# ADC_1CH.net
KiCad netlist of a schematic drawn in Altium Designer
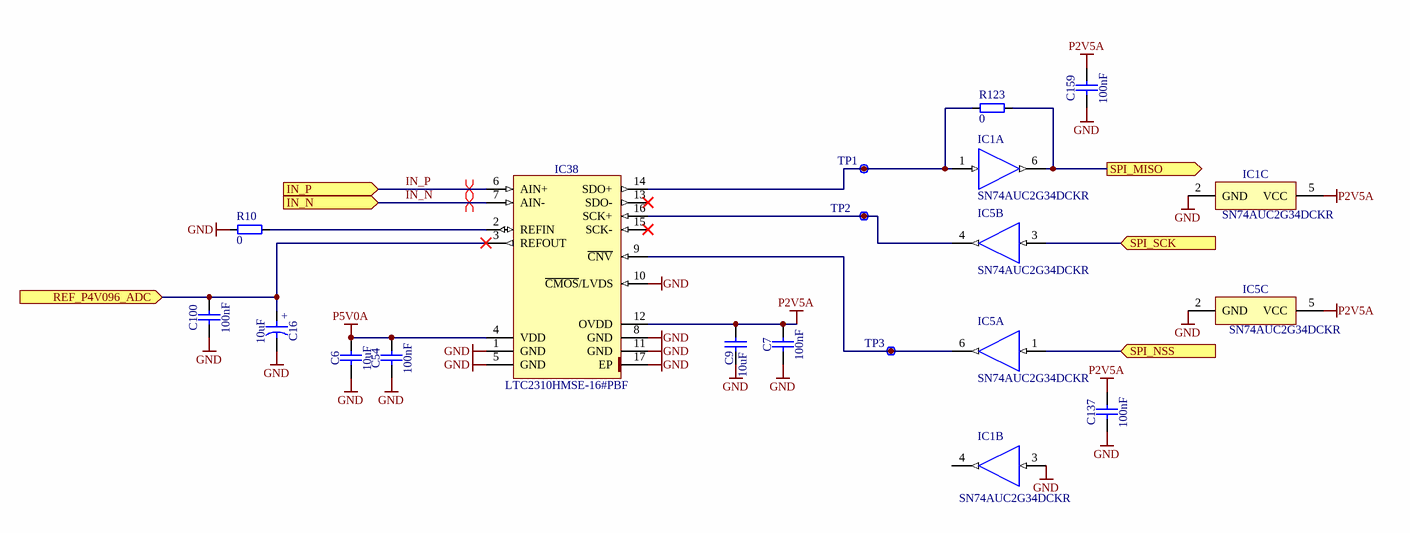
[diagram p0: ADC_1CH.SchDoc]

(export (version "E")
  (design (tool "Eeschema 10.0.6"))
  (components
    (comp (ref "C6")
      (value "10uF")
      (footprint "CAPC2012X95N")
      (description "Non-polarised capacitor")
      (fields
        (field (name "PART NUMBER") "CC0805_10UF_25V_10%_X5R")
        (field (name "VOLTAGE") "25V")
        (field (name "AUTHOR") "CERN DEM JLC")
      )
      (libsource (lib "Capacitors") (part "Capacitor - non polarized"))
    )
    (comp (ref "C7")
      (value "100nF")
      (footprint "CAPC1005X55N")
      (description "Non-polarised capacitor")
      (fields
        (field (name "PART NUMBER") "CC0402_100NF_16V_10%_X7R")
        (field (name "VOLTAGE") "16V")
        (field (name "AUTHOR") "CERN DEM JLC")
      )
      (libsource (lib "Capacitors") (part "Capacitor - non polarized"))
    )
    (comp (ref "C9")
      (value "10uF")
      (footprint "CAPC2012X95N")
      (description "Non-polarised capacitor")
      (fields
        (field (name "PART NUMBER") "CC0805_10UF_25V_10%_X5R")
        (field (name "VOLTAGE") "25V")
        (field (name "AUTHOR") "CERN DEM JLC")
      )
      (libsource (lib "Capacitors") (part "Capacitor - non polarized"))
    )
    (comp (ref "C16")
      (value "10uF")
      (footprint "CAPMP3216X180N")
      (description "Polarised capacitor")
      (fields
        (field (name "PART NUMBER") "CTE3216-18_10UF_16V_20%_AVX_TCJ")
        (field (name "VOLTAGE") "16V")
        (field (name "AUTHOR") "CERN DEM JLC")
      )
      (libsource (lib "Capacitors") (part "Capacitor - polarized"))
    )
    (comp (ref "C54")
      (value "100nF")
      (footprint "CAPC1005X55N")
      (description "Non-polarised capacitor")
      (fields
        (field (name "PART NUMBER") "CC0402_100NF_16V_10%_X7R")
        (field (name "VOLTAGE") "16V")
        (field (name "AUTHOR") "CERN DEM JLC")
      )
      (libsource (lib "Capacitors") (part "Capacitor - non polarized"))
    )
    (comp (ref "C100")
      (value "100nF")
      (footprint "CAPC1005X55N")
      (description "Non-polarised capacitor")
      (fields
        (field (name "PART NUMBER") "CC0402_100NF_16V_10%_X7R")
        (field (name "VOLTAGE") "16V")
        (field (name "AUTHOR") "CERN DEM JLC")
      )
      (libsource (lib "Capacitors") (part "Capacitor - non polarized"))
    )
    (comp (ref "C137")
      (value "100nF")
      (footprint "CAPC1005X55N")
      (description "Non-polarised capacitor")
      (fields
        (field (name "PART NUMBER") "CC0402_100NF_16V_10%_X7R")
        (field (name "VOLTAGE") "16V")
        (field (name "AUTHOR") "CERN DEM JLC")
      )
      (libsource (lib "Capacitors") (part "Capacitor - non polarized"))
    )
    (comp (ref "C159")
      (value "100nF")
      (footprint "CAPC1005X55N")
      (description "Non-polarised capacitor")
      (fields
        (field (name "PART NUMBER") "CC0402_100NF_16V_10%_X7R")
        (field (name "VOLTAGE") "16V")
        (field (name "AUTHOR") "CERN DEM JLC")
      )
      (libsource (lib "Capacitors") (part "Capacitor - non polarized"))
    )
    (comp (ref "IC1")
      (value "SN74AUC2G34DCKR")
      (footprint "DCK0006A_M")
      (description "Dual Buffer Gate, DCK0006A, LARGE T&R")
      (fields (field (name "PART NUMBER") "SN74AUC2G34"))
      (libsource (lib "") (part "TI-SN74XXX2GXXX-6_A_1"))
    )
    (comp (ref "IC5")
      (value "SN74AUC2G34DCKR")
      (footprint "DCK0006A_M")
      (description "Dual Buffer Gate, DCK0006A, LARGE T&R")
      (fields (field (name "PART NUMBER") "SN74AUC2G34"))
      (libsource (lib "Altium Content Vault") (part "TI-SN74XXX2GXXX-6_A"))
    )
    (comp (ref "IC38")
      (value "LTC2310HMSE-16#PBF")
      (footprint "SOP50P490X110-17N-R175X290")
      (description "16-Bit, 2Msps Differential Input ADC with Wide Input Common Mode Range")
      (fields (field (name "MANUFACTURER") "LINEAR TECHNOLOGY") (field (name "AUTHOR") "CERN DEM JLC"))
      (libsource (lib "ICs And Semiconductors") (part "LTC2310"))
    )
    (comp (ref "R10")
      (value "0")
      (footprint "RESC1005X40N")
      (description "Resistor")
      (fields
        (field (name "PART NUMBER") "R0402_0R_JUMPER")
        (field (name "MANUFACTURER") "GENERIC")
        (field (name "AUTHOR") "CERN DEM JLC")
      )
      (libsource (lib "Resistors") (part "Resistor"))
    )
    (comp (ref "R123")
      (value "0")
      (footprint "RESC1005X40N")
      (description "Resistor")
      (fields
        (field (name "PART NUMBER") "R0402_0R_JUMPER")
        (field (name "MANUFACTURER") "GENERIC")
        (field (name "AUTHOR") "CERN DEM JLC")
      )
      (libsource (lib "Resistors") (part "Resistor"))
    )
    (comp (ref "TP1")
      (value "Test Point")
      (footprint "TPS127")
      (fields (field (name "PART NUMBER") "SMD_PAD_1.27X1.27MM") (field (name "AUTHOR") "CERN DEM JLC"))
      (libsource (lib "Eletro-mechanical") (part "Test Point"))
    )
    (comp (ref "TP2")
      (value "Test Point")
      (footprint "TPS127")
      (fields (field (name "PART NUMBER") "SMD_PAD_1.27X1.27MM") (field (name "AUTHOR") "CERN DEM JLC"))
      (libsource (lib "Eletro-mechanical") (part "Test Point"))
    )
    (comp (ref "TP3")
      (value "Test Point")
      (footprint "TPS127")
      (fields (field (name "PART NUMBER") "SMD_PAD_1.27X1.27MM") (field (name "AUTHOR") "CERN DEM JLC"))
      (libsource (lib "Eletro-mechanical") (part "Test Point"))
    )
  )
  (nets
    (net (code "1") (name "/IN_N") (class "Default")
      (node (ref "IC38") (pin "7") (pinfunction "AIN-_7") (pintype "input"))
    )
    (net (code "2") (name "/IN_P") (class "Default")
      (node (ref "IC38") (pin "6") (pinfunction "AIN+_6") (pintype "input"))
    )
    (net (code "3") (name "/REF_P4V096_ADC") (class "Default")
      (node (ref "C100") (pin "2") (pinfunction "2_2") (pintype "passive"))
      (node (ref "C16") (pin "1") (pinfunction "1_1") (pintype "passive"))
      (node (ref "IC38") (pin "3") (pinfunction "REFOUT_3") (pintype "output"))
    )
    (net (code "4") (name "/SPI_MISO") (class "Default")
      (node (ref "IC1") (pin "6") (pinfunction "1Y_6") (pintype "output"))
      (node (ref "R123") (pin "2") (pinfunction "2_2") (pintype "passive"))
    )
    (net (code "5") (name "/SPI_NSS") (class "Default")
      (node (ref "IC5") (pin "1") (pinfunction "1A_1") (pintype "input"))
    )
    (net (code "6") (name "/SPI_SCK") (class "Default")
      (node (ref "IC5") (pin "3") (pinfunction "2A_3") (pintype "input"))
    )
    (net (code "7") (name "GND") (class "Default")
      (node (ref "C100") (pin "1") (pinfunction "1_1") (pintype "passive"))
      (node (ref "C137") (pin "1") (pinfunction "1_1") (pintype "passive"))
      (node (ref "C159") (pin "1") (pinfunction "1_1") (pintype "passive"))
      (node (ref "C16") (pin "2") (pinfunction "2_2") (pintype "passive"))
      (node (ref "C54") (pin "1") (pinfunction "1_1") (pintype "passive"))
      (node (ref "C6") (pin "1") (pinfunction "1_1") (pintype "passive"))
      (node (ref "C7") (pin "1") (pinfunction "1_1") (pintype "passive"))
      (node (ref "C9") (pin "1") (pinfunction "1_1") (pintype "passive"))
      (node (ref "IC1") (pin "2") (pinfunction "GND_2") (pintype "power_in"))
      (node (ref "IC1") (pin "3") (pinfunction "2A_3") (pintype "input"))
      (node (ref "IC38") (pin "1") (pinfunction "GND_1") (pintype "power_in"))
      (node (ref "IC38") (pin "10") (pinfunction "~{CMOS}/LVDS_10") (pintype "input"))
      (node (ref "IC38") (pin "11") (pinfunction "GND_11") (pintype "power_in"))
      (node (ref "IC38") (pin "17") (pinfunction "EP_17") (pintype "power_in"))
      (node (ref "IC38") (pin "5") (pinfunction "GND_5") (pintype "power_in"))
      (node (ref "IC38") (pin "8") (pinfunction "GND_8") (pintype "power_in"))
      (node (ref "IC5") (pin "2") (pinfunction "GND_2") (pintype "power_in"))
      (node (ref "R10") (pin "1") (pinfunction "1_1") (pintype "passive"))
    )
    (net (code "8") (name "Net-(IC1A-1A)") (class "Default")
      (node (ref "IC1") (pin "1") (pinfunction "1A_1") (pintype "input"))
      (node (ref "IC38") (pin "14") (pinfunction "SDO+_14") (pintype "output"))
      (node (ref "R123") (pin "1") (pinfunction "1_1") (pintype "passive"))
      (node (ref "TP1") (pin "1") (pinfunction "1_1") (pintype "bidirectional"))
    )
    (net (code "9") (name "Net-(IC38-REFIN)") (class "Default")
      (node (ref "IC38") (pin "2") (pinfunction "REFIN_2") (pintype "bidirectional"))
      (node (ref "R10") (pin "2") (pinfunction "2_2") (pintype "passive"))
    )
    (net (code "10") (name "Net-(IC38-SCK+)") (class "Default")
      (node (ref "IC38") (pin "16") (pinfunction "SCK+_16") (pintype "input"))
      (node (ref "IC5") (pin "4") (pinfunction "2Y_4") (pintype "output"))
      (node (ref "TP2") (pin "1") (pinfunction "1_1") (pintype "bidirectional"))
    )
    (net (code "11") (name "Net-(IC38-~{CNV})") (class "Default")
      (node (ref "IC38") (pin "9") (pinfunction "~{CNV}_9") (pintype "input"))
      (node (ref "IC5") (pin "6") (pinfunction "1Y_6") (pintype "output"))
      (node (ref "TP3") (pin "1") (pinfunction "1_1") (pintype "bidirectional"))
    )
    (net (code "12") (name "P2V5A") (class "Default")
      (node (ref "C137") (pin "2") (pinfunction "2_2") (pintype "passive"))
      (node (ref "C159") (pin "2") (pinfunction "2_2") (pintype "passive"))
      (node (ref "C7") (pin "2") (pinfunction "2_2") (pintype "passive"))
      (node (ref "C9") (pin "2") (pinfunction "2_2") (pintype "passive"))
      (node (ref "IC1") (pin "5") (pinfunction "VCC_5") (pintype "power_in"))
      (node (ref "IC38") (pin "12") (pinfunction "OVDD_12") (pintype "power_in"))
      (node (ref "IC5") (pin "5") (pinfunction "VCC_5") (pintype "power_in"))
    )
    (net (code "13") (name "P5V0A") (class "Default")
      (node (ref "C54") (pin "2") (pinfunction "2_2") (pintype "passive"))
      (node (ref "C6") (pin "2") (pinfunction "2_2") (pintype "passive"))
      (node (ref "IC38") (pin "4") (pinfunction "VDD_4") (pintype "power_in"))
    )
    (net (code "14") (name "unconnected-(IC1B-2Y-Pad4)") (class "Default")
      (node (ref "IC1") (pin "4") (pinfunction "2Y_4") (pintype "output"))
    )
    (net (code "15") (name "unconnected-(IC38-SCK--Pad15)") (class "Default")
      (node (ref "IC38") (pin "15") (pinfunction "SCK-_15") (pintype "input+no_connect"))
    )
    (net (code "16") (name "unconnected-(IC38-SDO--Pad13)") (class "Default")
      (node (ref "IC38") (pin "13") (pinfunction "SDO-_13") (pintype "output+no_connect"))
    )
  )
)
